# FLIPOP.net
KiCad netlist of a schematic drawn in EAGLE
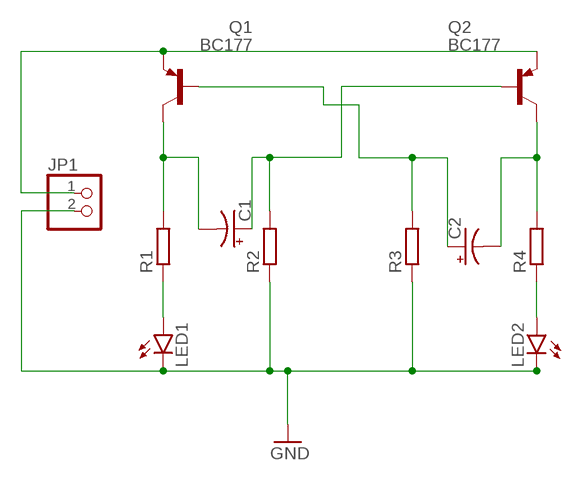
[diagram p0: schematic, sheet 1]

(export (version "E")
  (design (tool "Eeschema 10.0.6"))
  (components
    (comp (ref "C1")
      (value "CPOL-USE2.5-5")
      (footprint "eagle-import:E2,5-5")
      (libsource (lib "eagle-import") (part "CPOL-USE2.5-5"))
    )
    (comp (ref "C2")
      (value "CPOL-USE2.5-5")
      (footprint "eagle-import:E2,5-5")
      (libsource (lib "eagle-import") (part "CPOL-USE2.5-5"))
    )
    (comp (ref "JP1")
      (value "PINHD-1X2")
      (footprint "eagle-import:1X02")
      (libsource (lib "eagle-import") (part "PINHD-1X2"))
    )
    (comp (ref "LED1")
      (value "LED5MM")
      (footprint "eagle-import:LED5MM")
      (libsource (lib "eagle-import") (part "LED5MM"))
    )
    (comp (ref "LED2")
      (value "LED5MM")
      (footprint "eagle-import:LED5MM")
      (libsource (lib "eagle-import") (part "LED5MM"))
    )
    (comp (ref "Q1")
      (value "BC177")
      (footprint "eagle-import:TO18")
      (libsource (lib "eagle-import") (part "BC177"))
    )
    (comp (ref "Q2")
      (value "BC177")
      (footprint "eagle-import:TO18")
      (libsource (lib "eagle-import") (part "BC177"))
    )
    (comp (ref "R1")
      (value "R-EU_0207/15")
      (footprint "eagle-import:0207_15")
      (libsource (lib "eagle-import") (part "R-EU_0207/15"))
    )
    (comp (ref "R2")
      (value "R-EU_0207/15")
      (footprint "eagle-import:0207_15")
      (libsource (lib "eagle-import") (part "R-EU_0207/15"))
    )
    (comp (ref "R3")
      (value "R-EU_0207/15")
      (footprint "eagle-import:0207_15")
      (libsource (lib "eagle-import") (part "R-EU_0207/15"))
    )
    (comp (ref "R4")
      (value "R-EU_0207/15")
      (footprint "eagle-import:0207_15")
      (libsource (lib "eagle-import") (part "R-EU_0207/15"))
    )
  )
  (nets
    (net (code "1") (name "GND") (class "Default")
      (node (ref "JP1") (pin "2") (pinfunction "2_2") (pintype "passive"))
      (node (ref "LED1") (pin "K") (pinfunction "C_K") (pintype "passive"))
      (node (ref "LED2") (pin "K") (pinfunction "C_K") (pintype "passive"))
      (node (ref "R2") (pin "1") (pinfunction "1_1") (pintype "passive"))
      (node (ref "R3") (pin "1") (pinfunction "1_1") (pintype "passive"))
    )
    (net (code "2") (name "Net-(LED1-PadA)") (class "Default")
      (node (ref "LED1") (pin "A") (pinfunction "A_A") (pintype "passive"))
      (node (ref "R1") (pin "1") (pinfunction "1_1") (pintype "passive"))
    )
    (net (code "3") (name "Net-(LED2-PadA)") (class "Default")
      (node (ref "LED2") (pin "A") (pinfunction "A_A") (pintype "passive"))
      (node (ref "R4") (pin "1") (pinfunction "1_1") (pintype "passive"))
    )
    (net (code "4") (name "Net-(Q1-B)") (class "Default")
      (node (ref "C2") (pin "+") (pinfunction "+_+") (pintype "passive"))
      (node (ref "Q1") (pin "2") (pinfunction "B_2") (pintype "passive"))
      (node (ref "R3") (pin "2") (pinfunction "2_2") (pintype "passive"))
    )
    (net (code "5") (name "Net-(Q1-C)") (class "Default")
      (node (ref "C1") (pin "-") (pinfunction "-_-") (pintype "passive"))
      (node (ref "Q1") (pin "3") (pinfunction "C_3") (pintype "passive"))
      (node (ref "R1") (pin "2") (pinfunction "2_2") (pintype "passive"))
    )
    (net (code "6") (name "Net-(Q1-E)") (class "Default")
      (node (ref "JP1") (pin "1") (pinfunction "1_1") (pintype "passive"))
      (node (ref "Q1") (pin "1") (pinfunction "E_1") (pintype "passive"))
      (node (ref "Q2") (pin "1") (pinfunction "E_1") (pintype "passive"))
    )
    (net (code "7") (name "Net-(Q2-B)") (class "Default")
      (node (ref "C1") (pin "+") (pinfunction "+_+") (pintype "passive"))
      (node (ref "Q2") (pin "2") (pinfunction "B_2") (pintype "passive"))
      (node (ref "R2") (pin "2") (pinfunction "2_2") (pintype "passive"))
    )
    (net (code "8") (name "Net-(Q2-C)") (class "Default")
      (node (ref "C2") (pin "-") (pinfunction "-_-") (pintype "passive"))
      (node (ref "Q2") (pin "3") (pinfunction "C_3") (pintype "passive"))
      (node (ref "R4") (pin "2") (pinfunction "2_2") (pintype "passive"))
    )
  )
)
